# switch_control.net
KiCad netlist of a schematic drawn in Altium Designer
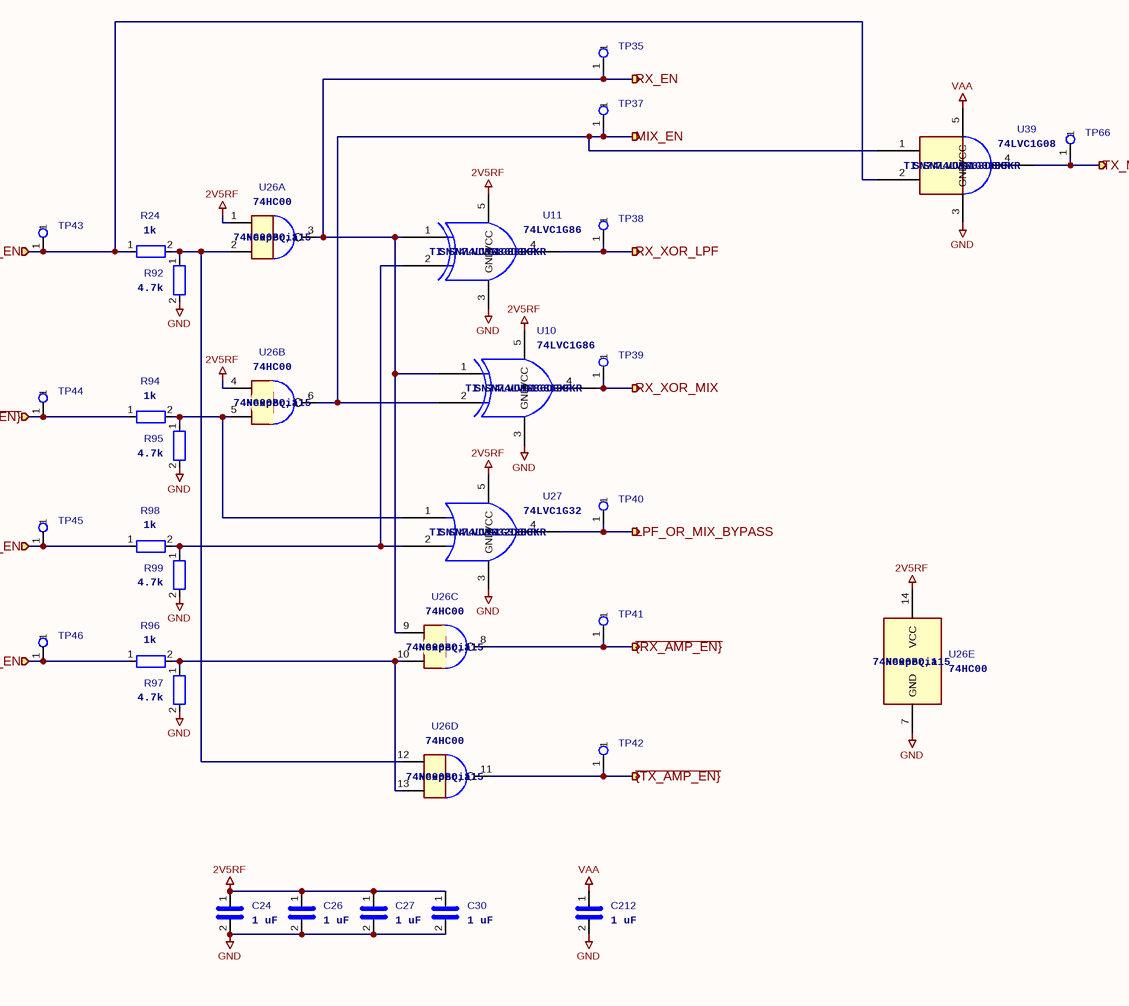
[diagram p0: switch_control.SchDoc]

(export (version "E")
  (design (tool "Eeschema 10.0.6"))
  (components
    (comp (ref "C24")
      (value "1 uF")
      (footprint "C_0201_0603Metric")
      (fields (field (name "MANUFACTURER") "Murata") (field (name "PART NUMBER") "GRM033R61A105ME44D"))
      (libsource (lib "Device") (part "C"))
    )
    (comp (ref "C26")
      (value "1 uF")
      (footprint "C_0201_0603Metric")
      (fields (field (name "MANUFACTURER") "Murata") (field (name "PART NUMBER") "GRM033R61A105ME44D"))
      (libsource (lib "Device") (part "C"))
    )
    (comp (ref "C27")
      (value "1 uF")
      (footprint "C_0201_0603Metric")
      (fields (field (name "MANUFACTURER") "Murata") (field (name "PART NUMBER") "GRM033R61A105ME44D"))
      (libsource (lib "Device") (part "C"))
    )
    (comp (ref "C30")
      (value "1 uF")
      (footprint "C_0201_0603Metric")
      (fields (field (name "MANUFACTURER") "Murata") (field (name "PART NUMBER") "GRM033R61A105ME44D"))
      (libsource (lib "Device") (part "C"))
    )
    (comp (ref "C212")
      (value "1 uF")
      (footprint "C_0201_0603Metric")
      (fields (field (name "MANUFACTURER") "Murata") (field (name "PART NUMBER") "GRM033R61A105ME44D"))
      (libsource (lib "Device") (part "C"))
    )
    (comp (ref "R24")
      (value "1k")
      (footprint "R_0201_0603Metric")
      (fields (field (name "MANUFACTURER") "Yageo") (field (name "PART NUMBER") "RC0201FR-071KL"))
      (libsource (lib "") (part "R_1"))
    )
    (comp (ref "R92")
      (value "4.7k")
      (footprint "R_0201_0603Metric")
      (fields (field (name "MANUFACTURER") "Yageo") (field (name "PART NUMBER") "RC0201FR-074K7L"))
      (libsource (lib "Device") (part "R"))
    )
    (comp (ref "R94")
      (value "1k")
      (footprint "R_0201_0603Metric")
      (fields (field (name "MANUFACTURER") "Yageo") (field (name "PART NUMBER") "RC0201FR-071KL"))
      (libsource (lib "") (part "R_1"))
    )
    (comp (ref "R95")
      (value "4.7k")
      (footprint "R_0201_0603Metric")
      (fields (field (name "MANUFACTURER") "Yageo") (field (name "PART NUMBER") "RC0201FR-074K7L"))
      (libsource (lib "Device") (part "R"))
    )
    (comp (ref "R96")
      (value "1k")
      (footprint "R_0201_0603Metric")
      (fields (field (name "MANUFACTURER") "Yageo") (field (name "PART NUMBER") "RC0201FR-071KL"))
      (libsource (lib "") (part "R_1"))
    )
    (comp (ref "R97")
      (value "4.7k")
      (footprint "R_0201_0603Metric")
      (fields (field (name "MANUFACTURER") "Yageo") (field (name "PART NUMBER") "RC0201FR-074K7L"))
      (libsource (lib "Device") (part "R"))
    )
    (comp (ref "R98")
      (value "1k")
      (footprint "R_0201_0603Metric")
      (fields (field (name "MANUFACTURER") "Yageo") (field (name "PART NUMBER") "RC0201FR-071KL"))
      (libsource (lib "") (part "R_1"))
    )
    (comp (ref "R99")
      (value "4.7k")
      (footprint "R_0201_0603Metric")
      (fields (field (name "MANUFACTURER") "Yageo") (field (name "PART NUMBER") "RC0201FR-074K7L"))
      (libsource (lib "Device") (part "R"))
    )
    (comp (ref "TP35")
      (value "TestPoint")
      (footprint "TestPoint_Pad_D1.0mm")
      (libsource (lib "Connector") (part "TestPoint"))
    )
    (comp (ref "TP37")
      (value "TestPoint")
      (footprint "TestPoint_Pad_D1.0mm")
      (libsource (lib "Connector") (part "TestPoint"))
    )
    (comp (ref "TP38")
      (value "TestPoint")
      (footprint "TestPoint_Pad_D1.0mm")
      (libsource (lib "Connector") (part "TestPoint"))
    )
    (comp (ref "TP39")
      (value "TestPoint")
      (footprint "TestPoint_Pad_D1.0mm")
      (libsource (lib "Connector") (part "TestPoint"))
    )
    (comp (ref "TP40")
      (value "TestPoint")
      (footprint "TestPoint_Pad_D1.0mm")
      (libsource (lib "Connector") (part "TestPoint"))
    )
    (comp (ref "TP41")
      (value "TestPoint")
      (footprint "TestPoint_Pad_D1.0mm")
      (libsource (lib "Connector") (part "TestPoint"))
    )
    (comp (ref "TP42")
      (value "TestPoint")
      (footprint "TestPoint_Pad_D1.0mm")
      (libsource (lib "Connector") (part "TestPoint"))
    )
    (comp (ref "TP43")
      (value "TestPoint")
      (footprint "TestPoint_Pad_D1.0mm")
      (libsource (lib "Connector") (part "TestPoint"))
    )
    (comp (ref "TP44")
      (value "TestPoint")
      (footprint "TestPoint_Pad_D1.0mm")
      (libsource (lib "Connector") (part "TestPoint"))
    )
    (comp (ref "TP45")
      (value "TestPoint")
      (footprint "TestPoint_Pad_D1.0mm")
      (libsource (lib "Connector") (part "TestPoint"))
    )
    (comp (ref "TP46")
      (value "TestPoint")
      (footprint "TestPoint_Pad_D1.0mm")
      (libsource (lib "Connector") (part "TestPoint"))
    )
    (comp (ref "TP66")
      (value "TestPoint")
      (footprint "TestPoint_Pad_D1.0mm")
      (libsource (lib "Connector") (part "TestPoint"))
    )
    (comp (ref "U10")
      (value "74LVC1G86")
      (footprint "SOT-353_SC-70-5")
      (fields
        (field (name "MANUFACTURER") "UMW")
        (field (name "PART NUMBER") "SN74LVC1G86DCKR")
        (field (name "SUBSTITUTION") "TI SN74LVC1G86DCKR")
      )
      (libsource (lib "74xGxx") (part "74LVC1G86"))
    )
    (comp (ref "U11")
      (value "74LVC1G86")
      (footprint "SOT-353_SC-70-5")
      (fields
        (field (name "MANUFACTURER") "UMW")
        (field (name "PART NUMBER") "SN74LVC1G86DCKR")
        (field (name "SUBSTITUTION") "TI SN74LVC1G86DCKR")
      )
      (libsource (lib "74xGxx") (part "74LVC1G86"))
    )
    (comp (ref "U26")
      (value "74HC00")
      (footprint "DHVQFN-14-1EP_2.5x3mm_P0.5mm_EP1x1.5mm")
      (fields (field (name "MANUFACTURER") "Nexperia") (field (name "PART NUMBER") "74HC00BQ,115"))
      (libsource (lib "74xx") (part "74HC00"))
    )
    (comp (ref "U27")
      (value "74LVC1G32")
      (footprint "SOT-353_SC-70-5")
      (fields
        (field (name "MANUFACTURER") "UMW")
        (field (name "PART NUMBER") "SN74LVC1G32DCKR")
        (field (name "SUBSTITUTION") "TI SN74LVC1G32DCKR")
      )
      (libsource (lib "74xGxx") (part "74LVC1G32"))
    )
    (comp (ref "U39")
      (value "74LVC1G08")
      (footprint "SOT-353_SC-70-5")
      (fields
        (field (name "MANUFACTURER") "UMW")
        (field (name "PART NUMBER") "SN74LVC1G08DCKR")
        (field (name "SUBSTITUTION") "TI SN74LVC1G08DCKR")
      )
      (libsource (lib "74xGxx") (part "74LVC1G08"))
    )
  )
  (nets
    (net (code "1") (name "/LPF_EN") (class "Default")
      (node (ref "R98") (pin "1") (pinfunction "1_1") (pintype "passive"))
      (node (ref "TP45") (pin "1") (pinfunction "1_1") (pintype "passive"))
    )
    (net (code "2") (name "/LPF_OR_MIX_BYPASS") (class "Default")
      (node (ref "TP40") (pin "1") (pinfunction "1_1") (pintype "passive"))
      (node (ref "U27") (pin "4") (pinfunction "4_4") (pintype "passive"))
    )
    (net (code "3") (name "/MIX_EN") (class "Default")
      (node (ref "TP37") (pin "1") (pinfunction "1_1") (pintype "passive"))
      (node (ref "U10") (pin "2") (pinfunction "2_2") (pintype "passive"))
      (node (ref "U26") (pin "6") (pinfunction "6_6") (pintype "passive"))
      (node (ref "U39") (pin "1") (pinfunction "1_1") (pintype "passive"))
    )
    (net (code "4") (name "/RF_AMP_EN") (class "Default")
      (node (ref "R96") (pin "1") (pinfunction "1_1") (pintype "passive"))
      (node (ref "TP46") (pin "1") (pinfunction "1_1") (pintype "passive"))
    )
    (net (code "5") (name "/RX_EN") (class "Default")
      (node (ref "TP35") (pin "1") (pinfunction "1_1") (pintype "passive"))
      (node (ref "U10") (pin "1") (pinfunction "1_1") (pintype "passive"))
      (node (ref "U11") (pin "1") (pinfunction "1_1") (pintype "passive"))
      (node (ref "U26") (pin "3") (pinfunction "3_3") (pintype "passive"))
      (node (ref "U26") (pin "9") (pinfunction "9_9") (pintype "passive"))
    )
    (net (code "6") (name "/RX_XOR_LPF") (class "Default")
      (node (ref "TP38") (pin "1") (pinfunction "1_1") (pintype "passive"))
      (node (ref "U11") (pin "4") (pinfunction "4_4") (pintype "passive"))
    )
    (net (code "7") (name "/RX_XOR_MIX") (class "Default")
      (node (ref "TP39") (pin "1") (pinfunction "1_1") (pintype "passive"))
      (node (ref "U10") (pin "4") (pinfunction "4_4") (pintype "passive"))
    )
    (net (code "8") (name "/TX_EN") (class "Default")
      (node (ref "R24") (pin "1") (pinfunction "1_1") (pintype "passive"))
      (node (ref "TP43") (pin "1") (pinfunction "1_1") (pintype "passive"))
      (node (ref "U39") (pin "2") (pinfunction "2_2") (pintype "passive"))
    )
    (net (code "9") (name "/TX_MIX_EN") (class "Default")
      (node (ref "TP66") (pin "1") (pinfunction "1_1") (pintype "passive"))
      (node (ref "U39") (pin "4") (pinfunction "4_4") (pintype "passive"))
    )
    (net (code "10") (name "/~{{MIX_EN}}") (class "Default")
      (node (ref "R94") (pin "1") (pinfunction "1_1") (pintype "passive"))
      (node (ref "TP44") (pin "1") (pinfunction "1_1") (pintype "passive"))
    )
    (net (code "11") (name "/~{{RX_AMP_EN}}") (class "Default")
      (node (ref "TP41") (pin "1") (pinfunction "1_1") (pintype "passive"))
      (node (ref "U26") (pin "8") (pinfunction "8_8") (pintype "passive"))
    )
    (net (code "12") (name "/~{{TX_AMP_EN}}") (class "Default")
      (node (ref "TP42") (pin "1") (pinfunction "1_1") (pintype "passive"))
      (node (ref "U26") (pin "11") (pinfunction "11_11") (pintype "passive"))
    )
    (net (code "13") (name "2V5RF") (class "Default")
      (node (ref "C24") (pin "1") (pinfunction "1_1") (pintype "passive"))
      (node (ref "C26") (pin "1") (pinfunction "1_1") (pintype "passive"))
      (node (ref "C27") (pin "1") (pinfunction "1_1") (pintype "passive"))
      (node (ref "C30") (pin "1") (pinfunction "1_1") (pintype "passive"))
      (node (ref "U10") (pin "5") (pinfunction "VCC_5") (pintype "passive"))
      (node (ref "U11") (pin "5") (pinfunction "VCC_5") (pintype "passive"))
      (node (ref "U26") (pin "1") (pinfunction "1_1") (pintype "passive"))
      (node (ref "U26") (pin "14") (pinfunction "VCC_14") (pintype "passive"))
      (node (ref "U26") (pin "4") (pinfunction "4_4") (pintype "passive"))
      (node (ref "U27") (pin "5") (pinfunction "VCC_5") (pintype "passive"))
    )
    (net (code "14") (name "GND") (class "Default")
      (node (ref "C212") (pin "2") (pinfunction "2_2") (pintype "passive"))
      (node (ref "C24") (pin "2") (pinfunction "2_2") (pintype "passive"))
      (node (ref "C26") (pin "2") (pinfunction "2_2") (pintype "passive"))
      (node (ref "C27") (pin "2") (pinfunction "2_2") (pintype "passive"))
      (node (ref "C30") (pin "2") (pinfunction "2_2") (pintype "passive"))
      (node (ref "R92") (pin "2") (pinfunction "2_2") (pintype "passive"))
      (node (ref "R95") (pin "2") (pinfunction "2_2") (pintype "passive"))
      (node (ref "R97") (pin "2") (pinfunction "2_2") (pintype "passive"))
      (node (ref "R99") (pin "2") (pinfunction "2_2") (pintype "passive"))
      (node (ref "U10") (pin "3") (pinfunction "GND_3") (pintype "passive"))
      (node (ref "U11") (pin "3") (pinfunction "GND_3") (pintype "passive"))
      (node (ref "U26") (pin "7") (pinfunction "GND_7") (pintype "passive"))
      (node (ref "U27") (pin "3") (pinfunction "GND_3") (pintype "passive"))
      (node (ref "U39") (pin "3") (pinfunction "GND_3") (pintype "passive"))
    )
    (net (code "15") (name "Net-(R24-Pad2)") (class "Default")
      (node (ref "R24") (pin "2") (pinfunction "2_2") (pintype "passive"))
      (node (ref "R92") (pin "1") (pinfunction "1_1") (pintype "passive"))
      (node (ref "U26") (pin "12") (pinfunction "12_12") (pintype "passive"))
      (node (ref "U26") (pin "2") (pinfunction "2_2") (pintype "passive"))
    )
    (net (code "16") (name "Net-(R94-Pad2)") (class "Default")
      (node (ref "R94") (pin "2") (pinfunction "2_2") (pintype "passive"))
      (node (ref "R95") (pin "1") (pinfunction "1_1") (pintype "passive"))
      (node (ref "U26") (pin "5") (pinfunction "5_5") (pintype "passive"))
      (node (ref "U27") (pin "1") (pinfunction "1_1") (pintype "passive"))
    )
    (net (code "17") (name "Net-(R96-Pad2)") (class "Default")
      (node (ref "R96") (pin "2") (pinfunction "2_2") (pintype "passive"))
      (node (ref "R97") (pin "1") (pinfunction "1_1") (pintype "passive"))
      (node (ref "U26") (pin "10") (pinfunction "10_10") (pintype "passive"))
      (node (ref "U26") (pin "13") (pinfunction "13_13") (pintype "passive"))
    )
    (net (code "18") (name "Net-(R98-Pad2)") (class "Default")
      (node (ref "R98") (pin "2") (pinfunction "2_2") (pintype "passive"))
      (node (ref "R99") (pin "1") (pinfunction "1_1") (pintype "passive"))
      (node (ref "U11") (pin "2") (pinfunction "2_2") (pintype "passive"))
      (node (ref "U27") (pin "2") (pinfunction "2_2") (pintype "passive"))
    )
    (net (code "19") (name "VAA") (class "Default")
      (node (ref "C212") (pin "1") (pinfunction "1_1") (pintype "passive"))
      (node (ref "U39") (pin "5") (pinfunction "VCC_5") (pintype "passive"))
    )
  )
)
